# Double_Socket_ESP-12.net
KiCad netlist of a schematic drawn in EAGLE
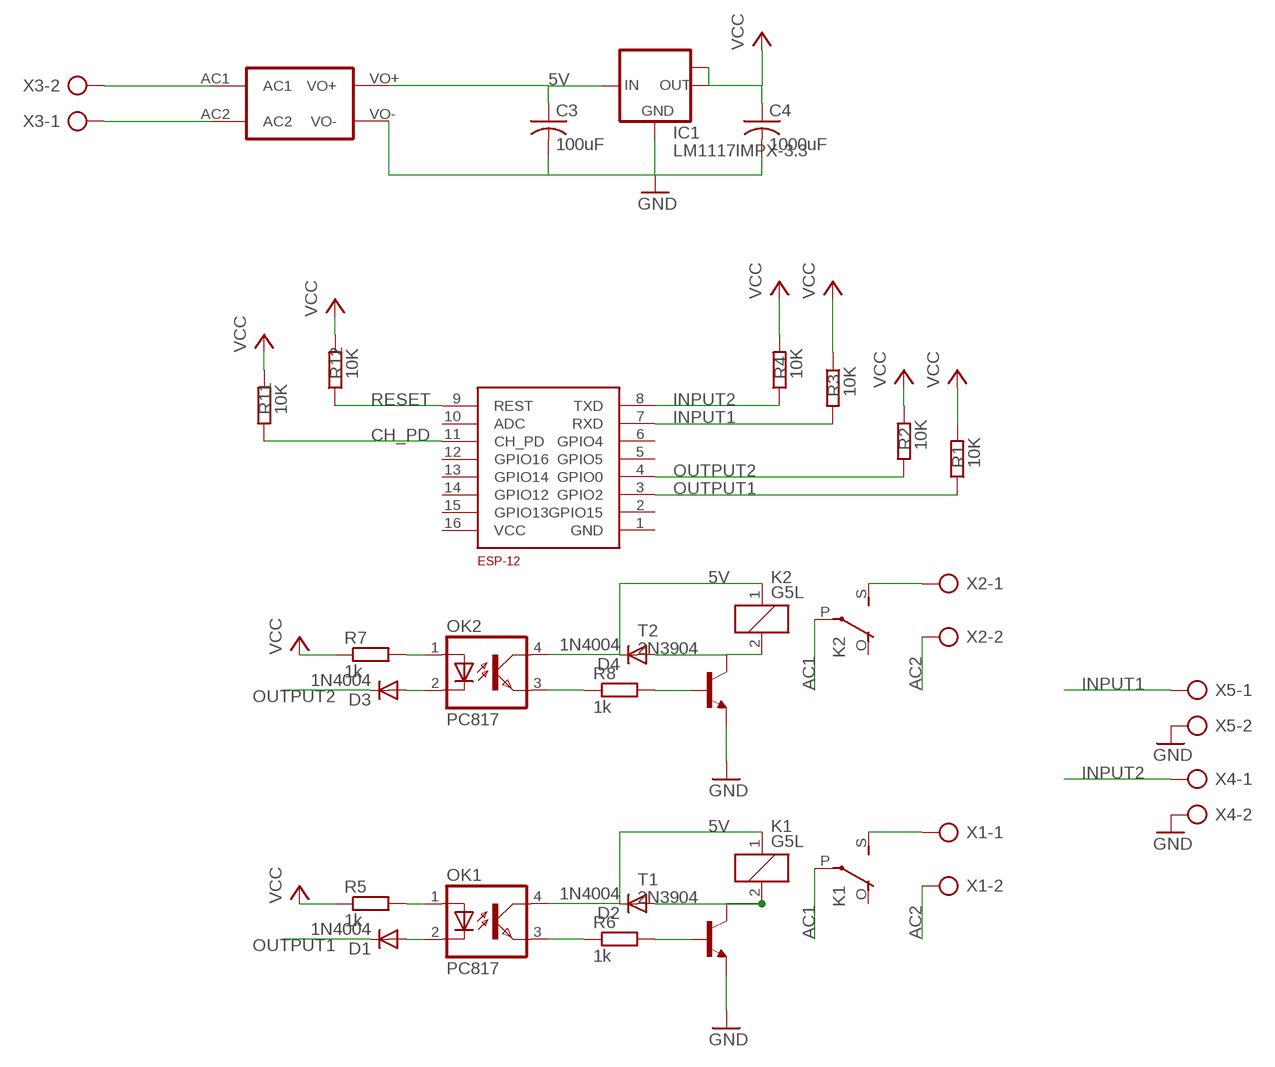
[diagram p0: schematic, sheet 1]

(export (version "E")
  (design (tool "Eeschema 10.0.6"))
  (components
    (comp (ref "C3")
      (value "100uF")
      (footprint "eagle-import:C0805")
      (libsource (lib "eagle-import") (part "C-USC0805"))
    )
    (comp (ref "C4")
      (value "1000uF")
      (footprint "eagle-import:C0805")
      (libsource (lib "eagle-import") (part "C-USC0805"))
    )
    (comp (ref "D1")
      (value "1N4004")
      (footprint "eagle-import:DO41-10")
      (libsource (lib "eagle-import") (part "1N4004"))
    )
    (comp (ref "D2")
      (value "1N4004")
      (footprint "eagle-import:DO41-10")
      (libsource (lib "eagle-import") (part "1N4004"))
    )
    (comp (ref "D3")
      (value "1N4004")
      (footprint "eagle-import:DO41-10")
      (libsource (lib "eagle-import") (part "1N4004"))
    )
    (comp (ref "D4")
      (value "1N4004")
      (footprint "eagle-import:DO41-10")
      (libsource (lib "eagle-import") (part "1N4004"))
    )
    (comp (ref "ESP-12")
      (value "ESP8266_ESP-12")
      (footprint "eagle-import:ESP8266-ESP12")
      (libsource (lib "eagle-import") (part "ESP8266_ESP-12"))
    )
    (comp (ref "IC1")
      (value "LM1117IMPX-3.3")
      (footprint "eagle-import:SOT223")
      (libsource (lib "eagle-import") (part "LM1117IMPX-3.3"))
    )
    (comp (ref "K1")
      (value "G5L")
      (footprint "eagle-import:G5LE")
      (libsource (lib "eagle-import") (part "G5L"))
    )
    (comp (ref "K2")
      (value "G5L")
      (footprint "eagle-import:G5LE")
      (libsource (lib "eagle-import") (part "G5L"))
    )
    (comp (ref "OK1")
      (value "PC817")
      (footprint "eagle-import:DIL04")
      (fields (field (name "MPN") "PC817X4J000F"))
      (libsource (lib "eagle-import") (part "PC817"))
    )
    (comp (ref "OK2")
      (value "PC817")
      (footprint "eagle-import:DIL04")
      (fields (field (name "MPN") "PC817X4J000F"))
      (libsource (lib "eagle-import") (part "PC817"))
    )
    (comp (ref "R1")
      (value "10K")
      (footprint "eagle-import:M0805")
      (libsource (lib "eagle-import") (part "R-EU_M0805"))
    )
    (comp (ref "R2")
      (value "10K")
      (footprint "eagle-import:M0805")
      (libsource (lib "eagle-import") (part "R-EU_M0805"))
    )
    (comp (ref "R3")
      (value "10K")
      (footprint "eagle-import:M0805")
      (libsource (lib "eagle-import") (part "R-EU_M0805"))
    )
    (comp (ref "R4")
      (value "10K")
      (footprint "eagle-import:M0805")
      (libsource (lib "eagle-import") (part "R-EU_M0805"))
    )
    (comp (ref "R5")
      (value "1k")
      (footprint "eagle-import:M0805")
      (libsource (lib "eagle-import") (part "R-EU_M0805"))
    )
    (comp (ref "R6")
      (value "1k")
      (footprint "eagle-import:M0805")
      (libsource (lib "eagle-import") (part "R-EU_M0805"))
    )
    (comp (ref "R7")
      (value "1k")
      (footprint "eagle-import:M0805")
      (libsource (lib "eagle-import") (part "R-EU_M0805"))
    )
    (comp (ref "R8")
      (value "1k")
      (footprint "eagle-import:M0805")
      (libsource (lib "eagle-import") (part "R-EU_M0805"))
    )
    (comp (ref "R11")
      (value "10K")
      (footprint "eagle-import:M0805")
      (libsource (lib "eagle-import") (part "R-EU_M0805"))
    )
    (comp (ref "R12")
      (value "10K")
      (footprint "eagle-import:M0805")
      (libsource (lib "eagle-import") (part "R-EU_M0805"))
    )
    (comp (ref "T1")
      (value "2N3904")
      (footprint "eagle-import:TO92")
      (libsource (lib "eagle-import") (part "2N3904"))
    )
    (comp (ref "T2")
      (value "2N3904")
      (footprint "eagle-import:TO92")
      (libsource (lib "eagle-import") (part "2N3904"))
    )
    (comp (ref "U$1")
      (value "HLK-PM01")
      (footprint "eagle-import:HLK-PM01")
      (libsource (lib "eagle-import") (part "HLK-PM01"))
    )
    (comp (ref "X1")
      (value "AK500/2-H")
      (footprint "eagle-import:AK500_2-H")
      (libsource (lib "eagle-import") (part "AK500/2-H"))
    )
    (comp (ref "X2")
      (value "AK500/2-H")
      (footprint "eagle-import:AK500_2-H")
      (libsource (lib "eagle-import") (part "AK500/2-H"))
    )
    (comp (ref "X3")
      (value "AK500/2-H")
      (footprint "eagle-import:AK500_2-H")
      (libsource (lib "eagle-import") (part "AK500/2-H"))
    )
    (comp (ref "X4")
      (value "AK500/2-H")
      (footprint "eagle-import:AK500_2-H")
      (libsource (lib "eagle-import") (part "AK500/2-H"))
    )
    (comp (ref "X5")
      (value "AK500/2-H")
      (footprint "eagle-import:AK500_2-H")
      (libsource (lib "eagle-import") (part "AK500/2-H"))
    )
  )
  (nets
    (net (code "1") (name "/5V") (class "Default")
      (node (ref "C3") (pin "1") (pinfunction "1_1") (pintype "passive"))
      (node (ref "D2") (pin "C") (pinfunction "C_C") (pintype "passive"))
      (node (ref "D4") (pin "C") (pinfunction "C_C") (pintype "passive"))
      (node (ref "IC1") (pin "3") (pinfunction "IN_3") (pintype "input"))
      (node (ref "K1") (pin "1") (pinfunction "1_1") (pintype "passive"))
      (node (ref "K2") (pin "1") (pinfunction "1_1") (pintype "passive"))
      (node (ref "OK1") (pin "4") (pinfunction "COL_4") (pintype "passive"))
      (node (ref "OK2") (pin "4") (pinfunction "COL_4") (pintype "passive"))
      (node (ref "U$1") (pin "VO+") (pinfunction "VO+_VO+") (pintype "bidirectional"))
    )
    (net (code "2") (name "/AC1") (class "Default")
      (node (ref "K1") (pin "P") (pinfunction "P_P") (pintype "passive"))
      (node (ref "K2") (pin "P") (pinfunction "P_P") (pintype "passive"))
      (node (ref "U$1") (pin "AC1") (pinfunction "AC1_AC1") (pintype "bidirectional"))
      (node (ref "X3") (pin "2") (pinfunction "KL_2") (pintype "passive"))
    )
    (net (code "3") (name "/AC2") (class "Default")
      (node (ref "U$1") (pin "AC2") (pinfunction "AC2_AC2") (pintype "bidirectional"))
      (node (ref "X1") (pin "2") (pinfunction "KL_2") (pintype "passive"))
      (node (ref "X2") (pin "2") (pinfunction "KL_2") (pintype "passive"))
      (node (ref "X3") (pin "1") (pinfunction "KL_1") (pintype "passive"))
    )
    (net (code "4") (name "/CH_PD") (class "Default")
      (node (ref "ESP-12") (pin "11") (pinfunction "CH_PD_11") (pintype "bidirectional"))
      (node (ref "R11") (pin "1") (pinfunction "1_1") (pintype "passive"))
    )
    (net (code "5") (name "/INPUT1") (class "Default")
      (node (ref "ESP-12") (pin "7") (pinfunction "RXD_7") (pintype "bidirectional"))
      (node (ref "R3") (pin "2") (pinfunction "2_2") (pintype "passive"))
      (node (ref "X5") (pin "1") (pinfunction "KL_1") (pintype "passive"))
    )
    (net (code "6") (name "/INPUT2") (class "Default")
      (node (ref "ESP-12") (pin "8") (pinfunction "TXD_8") (pintype "bidirectional"))
      (node (ref "R4") (pin "1") (pinfunction "1_1") (pintype "passive"))
      (node (ref "X4") (pin "1") (pinfunction "KL_1") (pintype "passive"))
    )
    (net (code "7") (name "/OUTPUT1") (class "Default")
      (node (ref "D1") (pin "C") (pinfunction "C_C") (pintype "passive"))
      (node (ref "ESP-12") (pin "3") (pinfunction "GPIO2_3") (pintype "bidirectional"))
      (node (ref "R1") (pin "1") (pinfunction "1_1") (pintype "passive"))
    )
    (net (code "8") (name "/OUTPUT2") (class "Default")
      (node (ref "D3") (pin "C") (pinfunction "C_C") (pintype "passive"))
      (node (ref "ESP-12") (pin "4") (pinfunction "GPIO0_4") (pintype "bidirectional"))
      (node (ref "R2") (pin "1") (pinfunction "1_1") (pintype "passive"))
    )
    (net (code "9") (name "/RESET") (class "Default")
      (node (ref "ESP-12") (pin "9") (pinfunction "REST_9") (pintype "bidirectional"))
      (node (ref "R12") (pin "1") (pinfunction "1_1") (pintype "passive"))
    )
    (net (code "10") (name "GND") (class "Default")
      (node (ref "C3") (pin "2") (pinfunction "2_2") (pintype "passive"))
      (node (ref "C4") (pin "2") (pinfunction "2_2") (pintype "passive"))
      (node (ref "IC1") (pin "1") (pinfunction "GND_1") (pintype "input"))
      (node (ref "T1") (pin "3") (pinfunction "E_3") (pintype "passive"))
      (node (ref "T2") (pin "3") (pinfunction "E_3") (pintype "passive"))
      (node (ref "U$1") (pin "VO-") (pinfunction "VO-_VO-") (pintype "bidirectional"))
      (node (ref "X4") (pin "2") (pinfunction "KL_2") (pintype "passive"))
      (node (ref "X5") (pin "2") (pinfunction "KL_2") (pintype "passive"))
    )
    (net (code "11") (name "Net-(OK1-A)") (class "Default")
      (node (ref "OK1") (pin "1") (pinfunction "A_1") (pintype "passive"))
      (node (ref "R5") (pin "2") (pinfunction "2_2") (pintype "passive"))
    )
    (net (code "12") (name "Net-(OK1-C)") (class "Default")
      (node (ref "D1") (pin "A") (pinfunction "A_A") (pintype "passive"))
      (node (ref "OK1") (pin "2") (pinfunction "C_2") (pintype "passive"))
    )
    (net (code "13") (name "Net-(OK1-EMIT)") (class "Default")
      (node (ref "OK1") (pin "3") (pinfunction "EMIT_3") (pintype "passive"))
      (node (ref "R6") (pin "1") (pinfunction "1_1") (pintype "passive"))
    )
    (net (code "14") (name "Net-(OK2-A)") (class "Default")
      (node (ref "OK2") (pin "1") (pinfunction "A_1") (pintype "passive"))
      (node (ref "R7") (pin "2") (pinfunction "2_2") (pintype "passive"))
    )
    (net (code "15") (name "Net-(OK2-C)") (class "Default")
      (node (ref "D3") (pin "A") (pinfunction "A_A") (pintype "passive"))
      (node (ref "OK2") (pin "2") (pinfunction "C_2") (pintype "passive"))
    )
    (net (code "16") (name "Net-(OK2-EMIT)") (class "Default")
      (node (ref "OK2") (pin "3") (pinfunction "EMIT_3") (pintype "passive"))
      (node (ref "R8") (pin "1") (pinfunction "1_1") (pintype "passive"))
    )
    (net (code "17") (name "Net-(T1-B)") (class "Default")
      (node (ref "R6") (pin "2") (pinfunction "2_2") (pintype "passive"))
      (node (ref "T1") (pin "2") (pinfunction "B_2") (pintype "passive"))
    )
    (net (code "18") (name "Net-(T1-C)") (class "Default")
      (node (ref "D2") (pin "A") (pinfunction "A_A") (pintype "passive"))
      (node (ref "K1") (pin "2") (pinfunction "2_2") (pintype "passive"))
      (node (ref "T1") (pin "1") (pinfunction "C_1") (pintype "passive"))
    )
    (net (code "19") (name "Net-(T2-B)") (class "Default")
      (node (ref "R8") (pin "2") (pinfunction "2_2") (pintype "passive"))
      (node (ref "T2") (pin "2") (pinfunction "B_2") (pintype "passive"))
    )
    (net (code "20") (name "Net-(T2-C)") (class "Default")
      (node (ref "D4") (pin "A") (pinfunction "A_A") (pintype "passive"))
      (node (ref "K2") (pin "2") (pinfunction "2_2") (pintype "passive"))
      (node (ref "T2") (pin "1") (pinfunction "C_1") (pintype "passive"))
    )
    (net (code "21") (name "Net-(X1A-KL)") (class "Default")
      (node (ref "K1") (pin "S") (pinfunction "S_S") (pintype "passive"))
      (node (ref "X1") (pin "1") (pinfunction "KL_1") (pintype "passive"))
    )
    (net (code "22") (name "Net-(X2A-KL)") (class "Default")
      (node (ref "K2") (pin "S") (pinfunction "S_S") (pintype "passive"))
      (node (ref "X2") (pin "1") (pinfunction "KL_1") (pintype "passive"))
    )
    (net (code "23") (name "VCC") (class "Default")
      (node (ref "C4") (pin "1") (pinfunction "1_1") (pintype "passive"))
      (node (ref "IC1") (pin "2") (pinfunction "OUT_2") (pintype "passive"))
      (node (ref "IC1") (pin "TAB") (pinfunction "OUT1_TAB") (pintype "passive"))
      (node (ref "R1") (pin "2") (pinfunction "2_2") (pintype "passive"))
      (node (ref "R11") (pin "2") (pinfunction "2_2") (pintype "passive"))
      (node (ref "R12") (pin "2") (pinfunction "2_2") (pintype "passive"))
      (node (ref "R2") (pin "2") (pinfunction "2_2") (pintype "passive"))
      (node (ref "R3") (pin "1") (pinfunction "1_1") (pintype "passive"))
      (node (ref "R4") (pin "2") (pinfunction "2_2") (pintype "passive"))
      (node (ref "R5") (pin "1") (pinfunction "1_1") (pintype "passive"))
      (node (ref "R7") (pin "1") (pinfunction "1_1") (pintype "passive"))
    )
    (net (code "24") (name "unconnected-(ESP-12-ADC-Pad10)") (class "Default")
      (node (ref "ESP-12") (pin "10") (pinfunction "ADC_10") (pintype "bidirectional"))
    )
    (net (code "25") (name "unconnected-(ESP-12-GND-Pad1)") (class "Default")
      (node (ref "ESP-12") (pin "1") (pinfunction "GND_1") (pintype "bidirectional"))
    )
    (net (code "26") (name "unconnected-(ESP-12-GPIO4-Pad6)") (class "Default")
      (node (ref "ESP-12") (pin "6") (pinfunction "GPIO4_6") (pintype "bidirectional"))
    )
    (net (code "27") (name "unconnected-(ESP-12-GPIO5-Pad5)") (class "Default")
      (node (ref "ESP-12") (pin "5") (pinfunction "GPIO5_5") (pintype "bidirectional"))
    )
    (net (code "28") (name "unconnected-(ESP-12-GPIO12-Pad14)") (class "Default")
      (node (ref "ESP-12") (pin "14") (pinfunction "GPIO12_14") (pintype "bidirectional"))
    )
    (net (code "29") (name "unconnected-(ESP-12-GPIO13-Pad15)") (class "Default")
      (node (ref "ESP-12") (pin "15") (pinfunction "GPIO13_15") (pintype "bidirectional"))
    )
    (net (code "30") (name "unconnected-(ESP-12-GPIO14-Pad13)") (class "Default")
      (node (ref "ESP-12") (pin "13") (pinfunction "GPIO14_13") (pintype "bidirectional"))
    )
    (net (code "31") (name "unconnected-(ESP-12-GPIO15-Pad2)") (class "Default")
      (node (ref "ESP-12") (pin "2") (pinfunction "GPIO15_2") (pintype "bidirectional"))
    )
    (net (code "32") (name "unconnected-(ESP-12-GPIO16-Pad12)") (class "Default")
      (node (ref "ESP-12") (pin "12") (pinfunction "GPIO16_12") (pintype "bidirectional"))
    )
    (net (code "33") (name "unconnected-(ESP-12-VCC-Pad16)") (class "Default")
      (node (ref "ESP-12") (pin "16") (pinfunction "VCC_16") (pintype "bidirectional"))
    )
    (net (code "34") (name "unconnected-(K1-PadO)") (class "Default")
      (node (ref "K1") (pin "O") (pinfunction "O_O") (pintype "passive"))
    )
    (net (code "35") (name "unconnected-(K2-PadO)") (class "Default")
      (node (ref "K2") (pin "O") (pinfunction "O_O") (pintype "passive"))
    )
  )
)
